# geiger_fixedR5R6.net
KiCad netlist of a schematic drawn in EAGLE
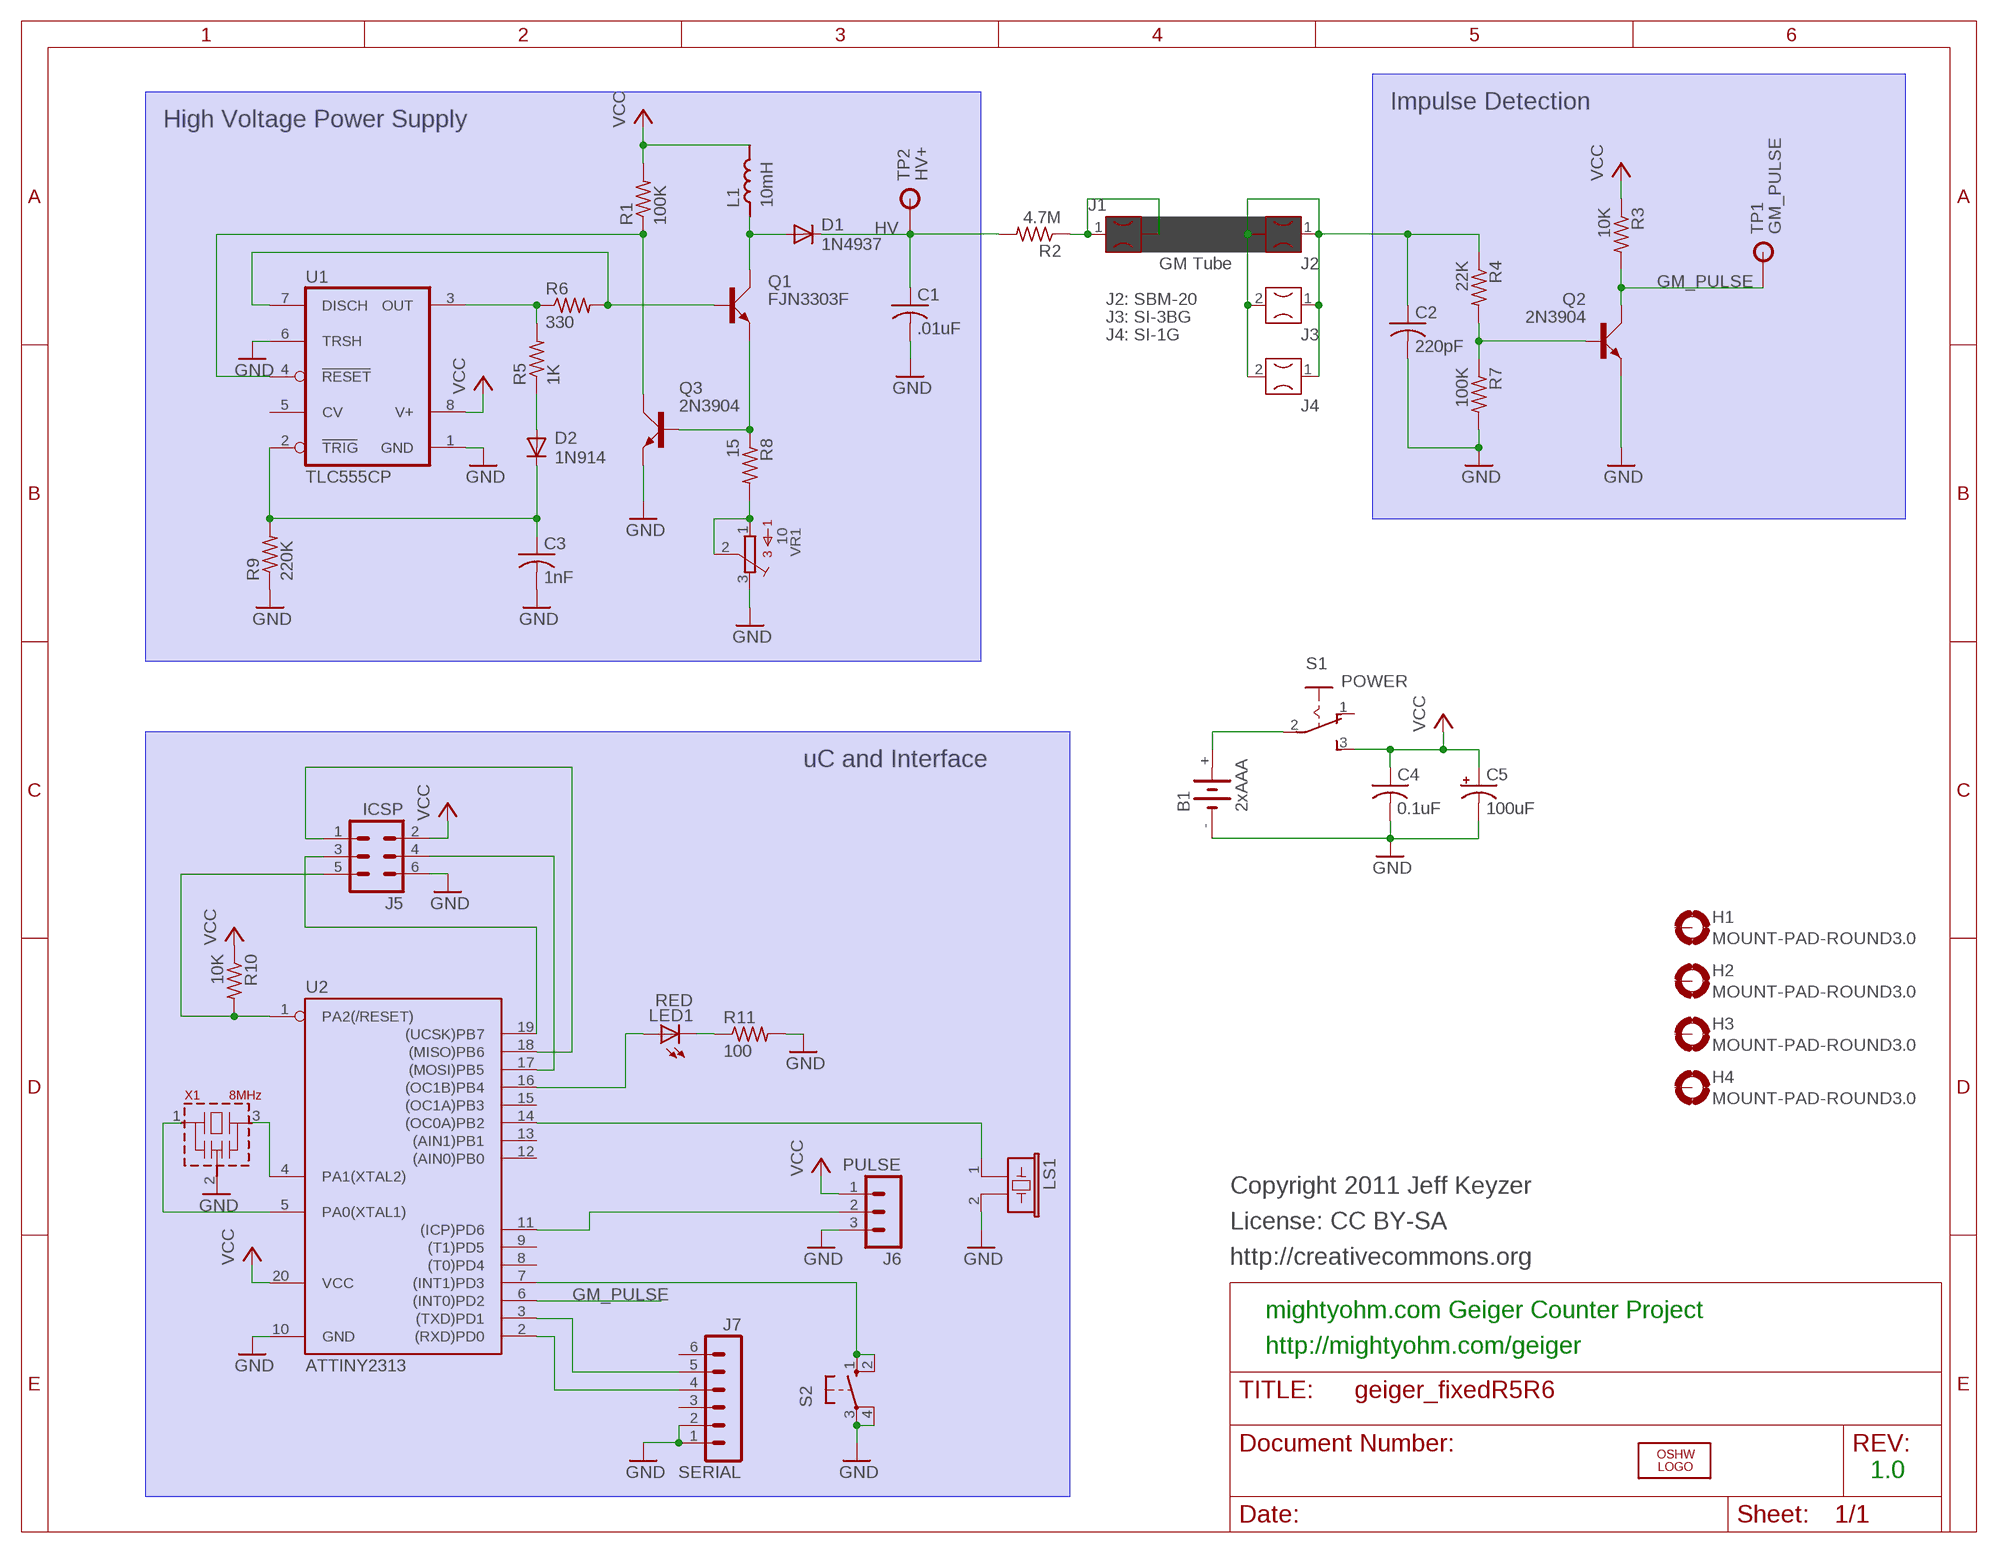
[diagram p0: schematic, sheet 1]

(export (version "E")
  (design (tool "Eeschema 10.0.6"))
  (components
    (comp (ref "B1")
      (value "2xAAA")
      (footprint "eagle-import:12BH423-GR")
      (libsource (lib "eagle-import") (part "BATTERY2XAAA_PCB"))
    )
    (comp (ref "C1")
      (value ".01uF")
      (footprint "eagle-import:C102-043X133")
      (libsource (lib "eagle-import") (part "C-US102-043X133"))
    )
    (comp (ref "C2")
      (value "220pF")
      (footprint "eagle-import:C050-030X075")
      (libsource (lib "eagle-import") (part "C-US050-030X075"))
    )
    (comp (ref "C3")
      (value "1nF")
      (footprint "eagle-import:C050-025X075")
      (libsource (lib "eagle-import") (part "C-US050-025X075"))
    )
    (comp (ref "C4")
      (value "0.1uF")
      (footprint "eagle-import:C025-025X050")
      (libsource (lib "eagle-import") (part "C-US025-025X050"))
    )
    (comp (ref "C5")
      (value "100uF")
      (footprint "eagle-import:E2,5-6")
      (libsource (lib "eagle-import") (part "CPOL-USE2.5-6"))
    )
    (comp (ref "D1")
      (value "1N4937")
      (footprint "eagle-import:DO41-10")
      (libsource (lib "eagle-import") (part "1N4933"))
    )
    (comp (ref "D2")
      (value "1N914")
      (footprint "eagle-import:DO35-7")
      (libsource (lib "eagle-import") (part "1N4148DO35-7"))
    )
    (comp (ref "H1")
      (value "MOUNT-PAD-ROUND3.0")
      (footprint "eagle-import:3,0-PAD")
      (libsource (lib "eagle-import") (part "MOUNT-PAD-ROUND3.0"))
    )
    (comp (ref "H2")
      (value "MOUNT-PAD-ROUND3.0")
      (footprint "eagle-import:3,0-PAD")
      (libsource (lib "eagle-import") (part "MOUNT-PAD-ROUND3.0"))
    )
    (comp (ref "H3")
      (value "MOUNT-PAD-ROUND3.0")
      (footprint "eagle-import:3,0-PAD")
      (libsource (lib "eagle-import") (part "MOUNT-PAD-ROUND3.0"))
    )
    (comp (ref "H4")
      (value "MOUNT-PAD-ROUND3.0")
      (footprint "eagle-import:3,0-PAD")
      (libsource (lib "eagle-import") (part "MOUNT-PAD-ROUND3.0"))
    )
    (comp (ref "J1")
      (value "FUSECLIPPCMOUNT")
      (footprint "eagle-import:FUSECLIP_PCMOUNT")
      (libsource (lib "eagle-import") (part "FUSECLIPPCMOUNT"))
    )
    (comp (ref "J2")
      (value "FUSECLIPPCMOUNT")
      (footprint "eagle-import:FUSECLIP_PCMOUNT")
      (libsource (lib "eagle-import") (part "FUSECLIPPCMOUNT"))
    )
    (comp (ref "J3")
      (value "FUSECLIPPCMOUNT")
      (footprint "eagle-import:FUSECLIP_PCMOUNT")
      (libsource (lib "eagle-import") (part "FUSECLIPPCMOUNT"))
    )
    (comp (ref "J4")
      (value "FUSECLIPPCMOUNT")
      (footprint "eagle-import:FUSECLIP_PCMOUNT")
      (libsource (lib "eagle-import") (part "FUSECLIPPCMOUNT"))
    )
    (comp (ref "J5")
      (value "ICSP")
      (footprint "eagle-import:ICSP-6")
      (libsource (lib "eagle-import") (part "ICSP-6"))
    )
    (comp (ref "J6")
      (value "PULSE")
      (footprint "eagle-import:MA03-1")
      (libsource (lib "eagle-import") (part "MA03-1"))
    )
    (comp (ref "J7")
      (value "SERIAL")
      (footprint "eagle-import:MA06-1")
      (libsource (lib "eagle-import") (part "MA06-1"))
    )
    (comp (ref "L1")
      (value "10mH")
      (footprint "eagle-import:ELC09D")
      (libsource (lib "eagle-import") (part "INDELC09D"))
    )
    (comp (ref "LED1")
      (value "RED")
      (footprint "eagle-import:LED5MM")
      (libsource (lib "eagle-import") (part "LED5MM"))
    )
    (comp (ref "LOGO1")
      (value "OSHW_LOGO_FILLX0200-NT")
      (footprint "eagle-import:OSHW_FILLX200_NOTEXT")
      (libsource (lib "eagle-import") (part "OSHW_LOGO_FILLX0200-NT"))
    )
    (comp (ref "LS1")
      (value "PIEZO17MM")
      (footprint "eagle-import:PS1740P02E")
      (libsource (lib "eagle-import") (part "PIEZO17MM"))
    )
    (comp (ref "Q1")
      (value "FJN3303F")
      (footprint "eagle-import:TO92C")
      (libsource (lib "eagle-import") (part "2N3704"))
    )
    (comp (ref "Q2")
      (value "2N3904")
      (footprint "eagle-import:TO92D")
      (libsource (lib "eagle-import") (part "2N3904"))
    )
    (comp (ref "Q3")
      (value "2N3904")
      (footprint "eagle-import:TO92D")
      (libsource (lib "eagle-import") (part "2N3904"))
    )
    (comp (ref "R1")
      (value "100K")
      (footprint "eagle-import:0207_10")
      (libsource (lib "eagle-import") (part "R-US_0207/10"))
    )
    (comp (ref "R2")
      (value "4.7M")
      (footprint "eagle-import:0207_10")
      (libsource (lib "eagle-import") (part "R-US_0207/10"))
    )
    (comp (ref "R3")
      (value "10K")
      (footprint "eagle-import:0207_10")
      (libsource (lib "eagle-import") (part "R-US_0207/10"))
    )
    (comp (ref "R4")
      (value "22K")
      (footprint "eagle-import:0207_10")
      (libsource (lib "eagle-import") (part "R-US_0207/10"))
    )
    (comp (ref "R5")
      (value "1K")
      (footprint "eagle-import:0207_10")
      (libsource (lib "eagle-import") (part "R-US_0207/10"))
    )
    (comp (ref "R6")
      (value "330")
      (footprint "eagle-import:0207_10")
      (libsource (lib "eagle-import") (part "R-US_0207/10"))
    )
    (comp (ref "R7")
      (value "100K")
      (footprint "eagle-import:0207_10")
      (libsource (lib "eagle-import") (part "R-US_0207/10"))
    )
    (comp (ref "R8")
      (value "15")
      (footprint "eagle-import:0207_10")
      (libsource (lib "eagle-import") (part "R-US_0207/10"))
    )
    (comp (ref "R9")
      (value "220K")
      (footprint "eagle-import:0207_10")
      (libsource (lib "eagle-import") (part "R-US_0207/10"))
    )
    (comp (ref "R10")
      (value "10K")
      (footprint "eagle-import:0207_10")
      (libsource (lib "eagle-import") (part "R-US_0207/10"))
    )
    (comp (ref "R11")
      (value "100")
      (footprint "eagle-import:0207_10")
      (libsource (lib "eagle-import") (part "R-US_0207/10"))
    )
    (comp (ref "S1")
      (value "POWER")
      (footprint "eagle-import:OS102011")
      (libsource (lib "eagle-import") (part "SWITCH_SPDT"))
    )
    (comp (ref "S2")
      (value "10-XX")
      (footprint "eagle-import:B3F-10XX")
      (libsource (lib "eagle-import") (part "10-XX"))
    )
    (comp (ref "TP1")
      (value "GM_PULSE")
      (footprint "eagle-import:TP_PTH")
      (libsource (lib "eagle-import") (part "TPPTH"))
    )
    (comp (ref "TP2")
      (value "HV+")
      (footprint "eagle-import:TP_PTH")
      (libsource (lib "eagle-import") (part "TPPTH"))
    )
    (comp (ref "U1")
      (value "TLC555CP")
      (footprint "eagle-import:DIL08")
      (libsource (lib "eagle-import") (part "ICM7555"))
    )
    (comp (ref "U2")
      (value "ATTINY2313")
      (footprint "eagle-import:DIL20")
      (libsource (lib "eagle-import") (part "TINY2313-P"))
    )
    (comp (ref "VR1")
      (value "10")
      (footprint "eagle-import:3386P")
      (libsource (lib "eagle-import") (part "3386-P"))
    )
    (comp (ref "X1")
      (value "8MHz")
      (footprint "eagle-import:CSTLA_T")
      (libsource (lib "eagle-import") (part "CSTLA_T"))
    )
  )
  (nets
    (net (code "1") (name "/GM_PULSE") (class "Default")
      (node (ref "Q2") (pin "C") (pinfunction "C_C") (pintype "passive"))
      (node (ref "R3") (pin "2") (pinfunction "2_2") (pintype "passive"))
      (node (ref "TP1") (pin "P$1") (pinfunction "TP_P$1") (pintype "bidirectional"))
      (node (ref "U2") (pin "6") (pinfunction "(INT0)PD2_6") (pintype "bidirectional"))
    )
    (net (code "2") (name "/HV") (class "Default")
      (node (ref "C1") (pin "1") (pinfunction "1_1") (pintype "passive"))
      (node (ref "D1") (pin "C") (pinfunction "C_C") (pintype "passive"))
      (node (ref "R2") (pin "2") (pinfunction "2_2") (pintype "passive"))
      (node (ref "TP2") (pin "P$1") (pinfunction "TP_P$1") (pintype "bidirectional"))
    )
    (net (code "3") (name "GND") (class "Default")
      (node (ref "B1") (pin "-") (pinfunction "-_-") (pintype "passive"))
      (node (ref "C1") (pin "2") (pinfunction "2_2") (pintype "passive"))
      (node (ref "C2") (pin "2") (pinfunction "2_2") (pintype "passive"))
      (node (ref "C3") (pin "2") (pinfunction "2_2") (pintype "passive"))
      (node (ref "C4") (pin "2") (pinfunction "2_2") (pintype "passive"))
      (node (ref "C5") (pin "-") (pinfunction "-_-") (pintype "passive"))
      (node (ref "J5") (pin "6") (pinfunction "6_6") (pintype "passive"))
      (node (ref "J6") (pin "3") (pinfunction "3_3") (pintype "passive"))
      (node (ref "J7") (pin "1") (pinfunction "1_1") (pintype "passive"))
      (node (ref "J7") (pin "2") (pinfunction "2_2") (pintype "passive"))
      (node (ref "LS1") (pin "2") (pinfunction "2_2") (pintype "passive"))
      (node (ref "Q2") (pin "E") (pinfunction "E_E") (pintype "passive"))
      (node (ref "Q3") (pin "E") (pinfunction "E_E") (pintype "passive"))
      (node (ref "R11") (pin "2") (pinfunction "2_2") (pintype "passive"))
      (node (ref "R7") (pin "2") (pinfunction "2_2") (pintype "passive"))
      (node (ref "R9") (pin "1") (pinfunction "1_1") (pintype "passive"))
      (node (ref "S2") (pin "3") (pinfunction "P_3") (pintype "passive"))
      (node (ref "S2") (pin "4") (pinfunction "P1_4") (pintype "passive"))
      (node (ref "U1") (pin "1") (pinfunction "GND_1") (pintype "power_in"))
      (node (ref "U1") (pin "6") (pinfunction "TRSH_6") (pintype "input"))
      (node (ref "U2") (pin "10") (pinfunction "GND_10") (pintype "power_in"))
      (node (ref "VR1") (pin "3") (pinfunction "3_3") (pintype "passive"))
      (node (ref "X1") (pin "2") (pinfunction "VSS_2") (pintype "power_in"))
    )
    (net (code "4") (name "Net-(B1-Pad+)") (class "Default")
      (node (ref "B1") (pin "+") (pinfunction "+_+") (pintype "passive"))
      (node (ref "S1") (pin "2") (pinfunction "2_2") (pintype "passive"))
    )
    (net (code "5") (name "Net-(C2-Pad1)") (class "Default")
      (node (ref "C2") (pin "1") (pinfunction "1_1") (pintype "passive"))
      (node (ref "J2") (pin "1") (pinfunction "1_1") (pintype "bidirectional"))
      (node (ref "J2") (pin "2") (pinfunction "2_2") (pintype "bidirectional"))
      (node (ref "J3") (pin "1") (pinfunction "1_1") (pintype "bidirectional"))
      (node (ref "J3") (pin "2") (pinfunction "2_2") (pintype "bidirectional"))
      (node (ref "J4") (pin "1") (pinfunction "1_1") (pintype "bidirectional"))
      (node (ref "J4") (pin "2") (pinfunction "2_2") (pintype "bidirectional"))
      (node (ref "R4") (pin "1") (pinfunction "1_1") (pintype "passive"))
    )
    (net (code "6") (name "Net-(D1-PadA)") (class "Default")
      (node (ref "D1") (pin "A") (pinfunction "A_A") (pintype "passive"))
      (node (ref "L1") (pin "1") (pinfunction "1_1") (pintype "passive"))
      (node (ref "Q1") (pin "C") (pinfunction "C_C") (pintype "passive"))
    )
    (net (code "7") (name "Net-(D2-PadA)") (class "Default")
      (node (ref "D2") (pin "A") (pinfunction "A_A") (pintype "passive"))
      (node (ref "R5") (pin "1") (pinfunction "1_1") (pintype "passive"))
    )
    (net (code "8") (name "Net-(J1-Pad1)") (class "Default")
      (node (ref "J1") (pin "1") (pinfunction "1_1") (pintype "bidirectional"))
      (node (ref "J1") (pin "2") (pinfunction "2_2") (pintype "bidirectional"))
      (node (ref "R2") (pin "1") (pinfunction "1_1") (pintype "passive"))
    )
    (net (code "9") (name "Net-(LED1-C)") (class "Default")
      (node (ref "LED1") (pin "K") (pinfunction "C_K") (pintype "passive"))
      (node (ref "R11") (pin "1") (pinfunction "1_1") (pintype "passive"))
    )
    (net (code "10") (name "Net-(Q1-PadE)") (class "Default")
      (node (ref "Q1") (pin "E") (pinfunction "E_E") (pintype "passive"))
      (node (ref "Q3") (pin "B") (pinfunction "B_B") (pintype "passive"))
      (node (ref "R8") (pin "1") (pinfunction "1_1") (pintype "passive"))
    )
    (net (code "11") (name "Net-(Q2-PadB)") (class "Default")
      (node (ref "Q2") (pin "B") (pinfunction "B_B") (pintype "passive"))
      (node (ref "R4") (pin "2") (pinfunction "2_2") (pintype "passive"))
      (node (ref "R7") (pin "1") (pinfunction "1_1") (pintype "passive"))
    )
    (net (code "12") (name "Net-(R8-Pad2)") (class "Default")
      (node (ref "R8") (pin "2") (pinfunction "2_2") (pintype "passive"))
      (node (ref "VR1") (pin "1") (pinfunction "1_1") (pintype "passive"))
      (node (ref "VR1") (pin "2") (pinfunction "2_2") (pintype "passive"))
    )
    (net (code "13") (name "Net-(S2-S)") (class "Default")
      (node (ref "S2") (pin "1") (pinfunction "S_1") (pintype "passive"))
      (node (ref "S2") (pin "2") (pinfunction "S1_2") (pintype "passive"))
      (node (ref "U2") (pin "7") (pinfunction "(INT1)PD3_7") (pintype "bidirectional"))
    )
    (net (code "14") (name "Net-(U1-DISCH)") (class "Default")
      (node (ref "Q1") (pin "B") (pinfunction "B_B") (pintype "passive"))
      (node (ref "R6") (pin "2") (pinfunction "2_2") (pintype "passive"))
      (node (ref "U1") (pin "7") (pinfunction "DISCH_7") (pintype "input"))
    )
    (net (code "15") (name "Net-(U1-OUT)") (class "Default")
      (node (ref "R5") (pin "2") (pinfunction "2_2") (pintype "passive"))
      (node (ref "R6") (pin "1") (pinfunction "1_1") (pintype "passive"))
      (node (ref "U1") (pin "3") (pinfunction "OUT_3") (pintype "output"))
    )
    (net (code "16") (name "Net-(U1-RESET)") (class "Default")
      (node (ref "Q3") (pin "C") (pinfunction "C_C") (pintype "passive"))
      (node (ref "R1") (pin "1") (pinfunction "1_1") (pintype "passive"))
      (node (ref "U1") (pin "4") (pinfunction "RESET_4") (pintype "input"))
    )
    (net (code "17") (name "Net-(U1-TRIG)") (class "Default")
      (node (ref "C3") (pin "1") (pinfunction "1_1") (pintype "passive"))
      (node (ref "D2") (pin "C") (pinfunction "C_C") (pintype "passive"))
      (node (ref "R9") (pin "2") (pinfunction "2_2") (pintype "passive"))
      (node (ref "U1") (pin "2") (pinfunction "TRIG_2") (pintype "bidirectional"))
    )
    (net (code "18") (name "Net-(U2-(ICP)PD6)") (class "Default")
      (node (ref "J6") (pin "2") (pinfunction "2_2") (pintype "passive"))
      (node (ref "U2") (pin "11") (pinfunction "(ICP)PD6_11") (pintype "bidirectional"))
    )
    (net (code "19") (name "Net-(U2-(MISO)PB6)") (class "Default")
      (node (ref "J5") (pin "1") (pinfunction "1_1") (pintype "passive"))
      (node (ref "U2") (pin "18") (pinfunction "(MISO)PB6_18") (pintype "bidirectional"))
    )
    (net (code "20") (name "Net-(U2-(MOSI)PB5)") (class "Default")
      (node (ref "J5") (pin "4") (pinfunction "4_4") (pintype "passive"))
      (node (ref "U2") (pin "17") (pinfunction "(MOSI)PB5_17") (pintype "bidirectional"))
    )
    (net (code "21") (name "Net-(U2-(OC0A)PB2)") (class "Default")
      (node (ref "LS1") (pin "1") (pinfunction "1_1") (pintype "passive"))
      (node (ref "U2") (pin "14") (pinfunction "(OC0A)PB2_14") (pintype "bidirectional"))
    )
    (net (code "22") (name "Net-(U2-(OC1B)PB4)") (class "Default")
      (node (ref "LED1") (pin "A") (pinfunction "A_A") (pintype "passive"))
      (node (ref "U2") (pin "16") (pinfunction "(OC1B)PB4_16") (pintype "bidirectional"))
    )
    (net (code "23") (name "Net-(U2-(RXD)PD0)") (class "Default")
      (node (ref "J7") (pin "4") (pinfunction "4_4") (pintype "passive"))
      (node (ref "U2") (pin "2") (pinfunction "(RXD)PD0_2") (pintype "bidirectional"))
    )
    (net (code "24") (name "Net-(U2-(TXD)PD1)") (class "Default")
      (node (ref "J7") (pin "5") (pinfunction "5_5") (pintype "passive"))
      (node (ref "U2") (pin "3") (pinfunction "(TXD)PD1_3") (pintype "bidirectional"))
    )
    (net (code "25") (name "Net-(U2-(UCSK)PB7)") (class "Default")
      (node (ref "J5") (pin "3") (pinfunction "3_3") (pintype "passive"))
      (node (ref "U2") (pin "19") (pinfunction "(UCSK)PB7_19") (pintype "bidirectional"))
    )
    (net (code "26") (name "Net-(U2-PA0(XTAL1))") (class "Default")
      (node (ref "U2") (pin "5") (pinfunction "PA0(XTAL1)_5") (pintype "bidirectional"))
      (node (ref "X1") (pin "1") (pinfunction "1_1") (pintype "output"))
    )
    (net (code "27") (name "Net-(U2-PA1(XTAL2))") (class "Default")
      (node (ref "U2") (pin "4") (pinfunction "PA1(XTAL2)_4") (pintype "bidirectional"))
      (node (ref "X1") (pin "3") (pinfunction "3_3") (pintype "input"))
    )
    (net (code "28") (name "Net-(U2-PA2({slash}RESET))") (class "Default")
      (node (ref "J5") (pin "5") (pinfunction "5_5") (pintype "passive"))
      (node (ref "R10") (pin "2") (pinfunction "2_2") (pintype "passive"))
      (node (ref "U2") (pin "1") (pinfunction "PA2(/RESET)_1") (pintype "input"))
    )
    (net (code "29") (name "VCC") (class "Default")
      (node (ref "C4") (pin "1") (pinfunction "1_1") (pintype "passive"))
      (node (ref "C5") (pin "+") (pinfunction "+_+") (pintype "passive"))
      (node (ref "J5") (pin "2") (pinfunction "2_2") (pintype "passive"))
      (node (ref "J6") (pin "1") (pinfunction "1_1") (pintype "passive"))
      (node (ref "L1") (pin "2") (pinfunction "2_2") (pintype "passive"))
      (node (ref "R1") (pin "2") (pinfunction "2_2") (pintype "passive"))
      (node (ref "R10") (pin "1") (pinfunction "1_1") (pintype "passive"))
      (node (ref "R3") (pin "1") (pinfunction "1_1") (pintype "passive"))
      (node (ref "S1") (pin "3") (pinfunction "3_3") (pintype "passive"))
      (node (ref "U1") (pin "8") (pinfunction "V+_8") (pintype "power_in"))
      (node (ref "U2") (pin "20") (pinfunction "VCC_20") (pintype "power_in"))
    )
    (net (code "30") (name "unconnected-(H1-MOUNT-PadB3,0)") (class "Default")
      (node (ref "H1") (pin "B3,0") (pinfunction "MOUNT_B3,0") (pintype "passive"))
    )
    (net (code "31") (name "unconnected-(H2-MOUNT-PadB3,0)") (class "Default")
      (node (ref "H2") (pin "B3,0") (pinfunction "MOUNT_B3,0") (pintype "passive"))
    )
    (net (code "32") (name "unconnected-(H3-MOUNT-PadB3,0)") (class "Default")
      (node (ref "H3") (pin "B3,0") (pinfunction "MOUNT_B3,0") (pintype "passive"))
    )
    (net (code "33") (name "unconnected-(H4-MOUNT-PadB3,0)") (class "Default")
      (node (ref "H4") (pin "B3,0") (pinfunction "MOUNT_B3,0") (pintype "passive"))
    )
    (net (code "34") (name "unconnected-(J7-Pad3)") (class "Default")
      (node (ref "J7") (pin "3") (pinfunction "3_3") (pintype "passive"))
    )
    (net (code "35") (name "unconnected-(J7-Pad6)") (class "Default")
      (node (ref "J7") (pin "6") (pinfunction "6_6") (pintype "passive"))
    )
    (net (code "36") (name "unconnected-(S1-Pad1)") (class "Default")
      (node (ref "S1") (pin "1") (pinfunction "1_1") (pintype "passive"))
    )
    (net (code "37") (name "unconnected-(U1-CV-Pad5)") (class "Default")
      (node (ref "U1") (pin "5") (pinfunction "CV_5") (pintype "passive"))
    )
    (net (code "38") (name "unconnected-(U2-(AIN0)PB0-Pad12)") (class "Default")
      (node (ref "U2") (pin "12") (pinfunction "(AIN0)PB0_12") (pintype "bidirectional"))
    )
    (net (code "39") (name "unconnected-(U2-(AIN1)PB1-Pad13)") (class "Default")
      (node (ref "U2") (pin "13") (pinfunction "(AIN1)PB1_13") (pintype "bidirectional"))
    )
    (net (code "40") (name "unconnected-(U2-(OC1A)PB3-Pad15)") (class "Default")
      (node (ref "U2") (pin "15") (pinfunction "(OC1A)PB3_15") (pintype "bidirectional"))
    )
    (net (code "41") (name "unconnected-(U2-(T0)PD4-Pad8)") (class "Default")
      (node (ref "U2") (pin "8") (pinfunction "(T0)PD4_8") (pintype "bidirectional"))
    )
    (net (code "42") (name "unconnected-(U2-(T1)PD5-Pad9)") (class "Default")
      (node (ref "U2") (pin "9") (pinfunction "(T1)PD5_9") (pintype "bidirectional"))
    )
  )
)
